# SPhotoDiode.net
KiCad netlist of a schematic drawn in EAGLE
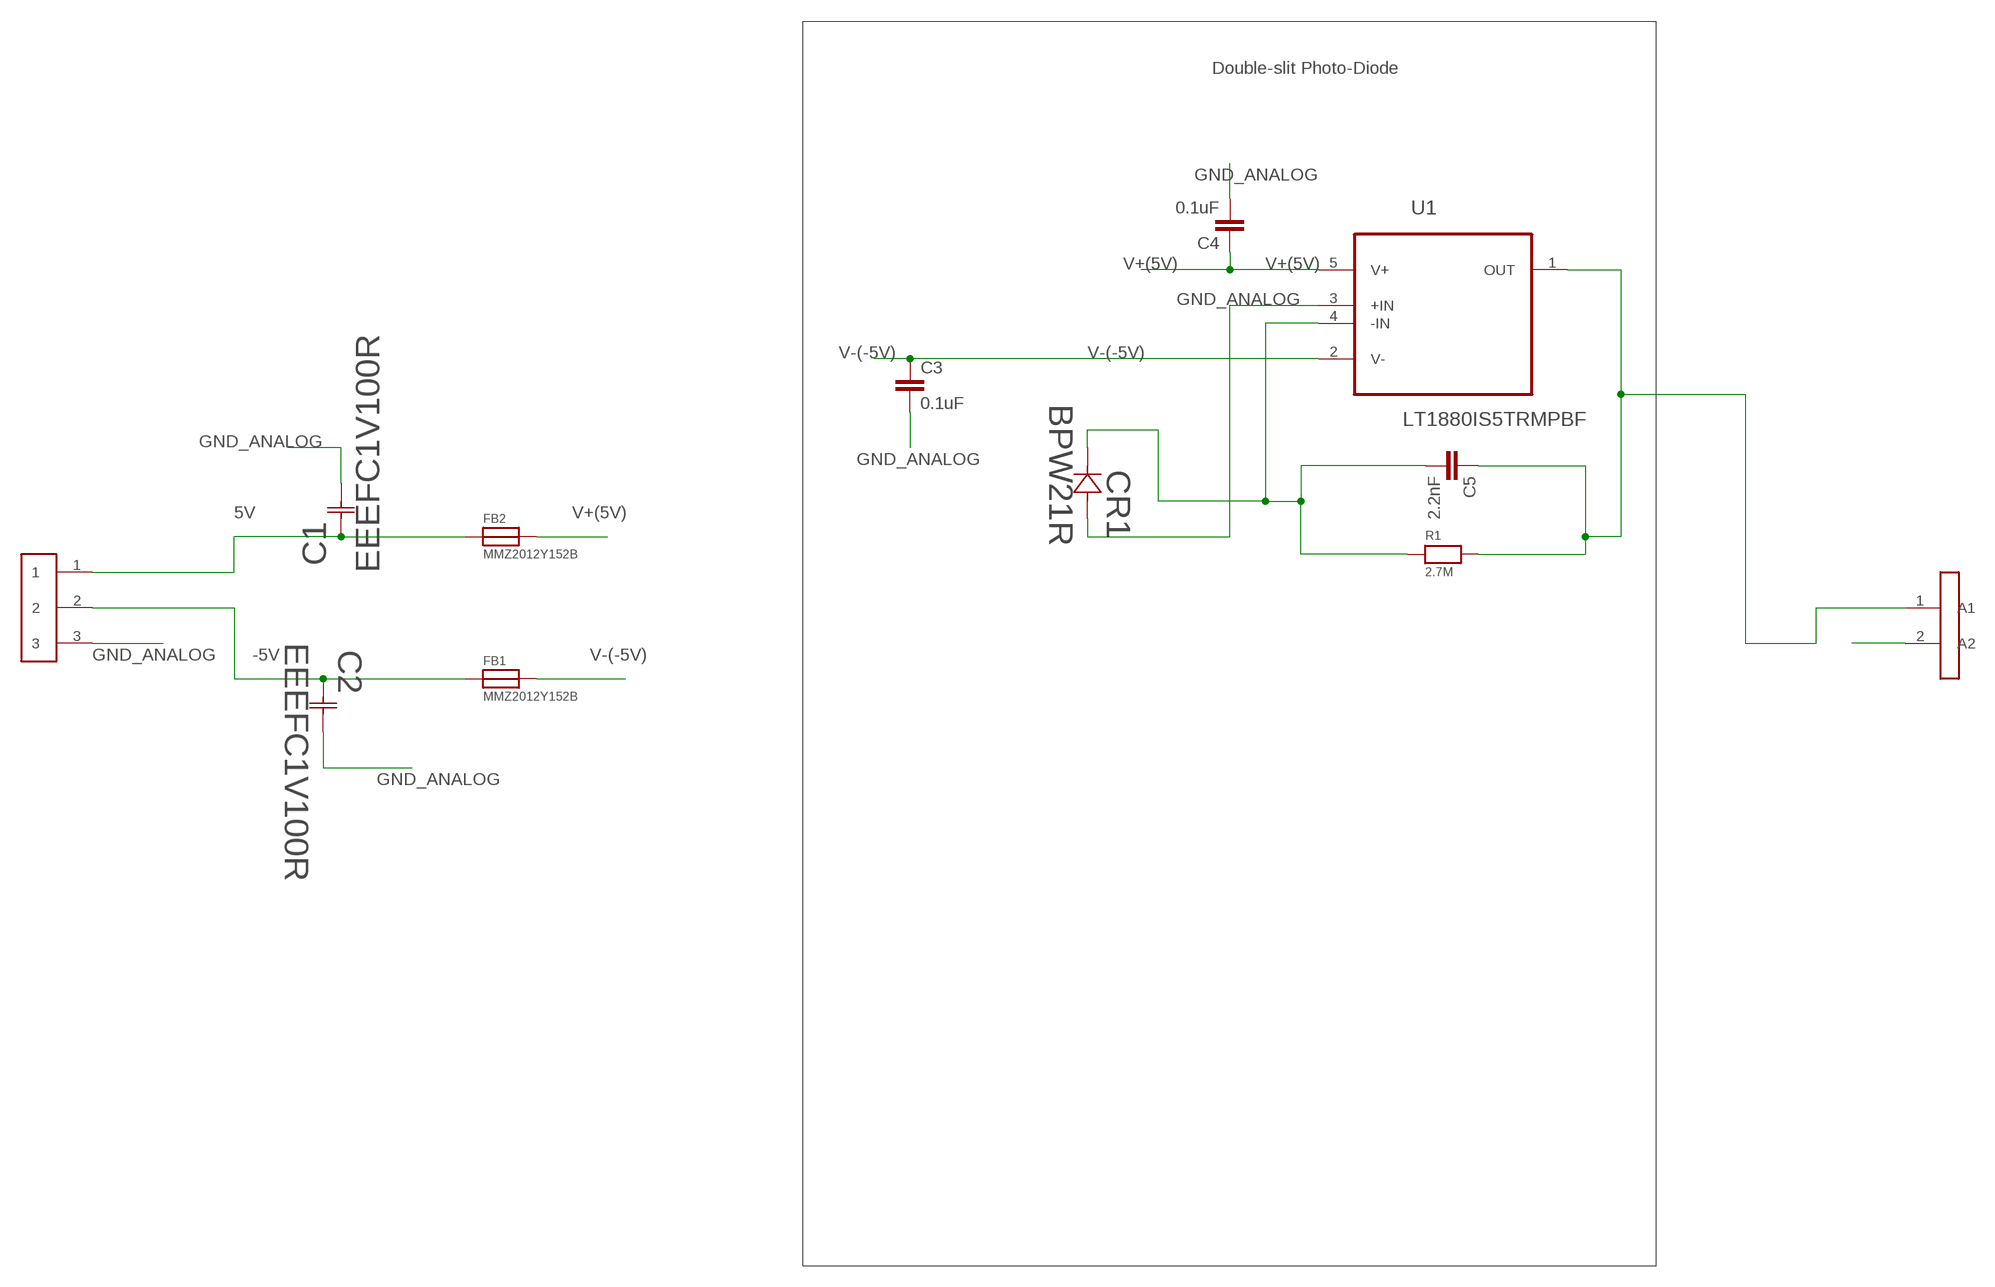
[diagram p0: schematic, sheet 1]

(export (version "E")
  (design (tool "Eeschema 10.0.6"))
  (components
    (comp (ref "C1")
      (value "EEEFC1V100R")
      (footprint "eagle-import:CAP_EEFC_C")
      (libsource (lib "eagle-import") (part "EEEFC1V100R"))
    )
    (comp (ref "C2")
      (value "EEEFC1V100R")
      (footprint "eagle-import:CAP_EEFC_C")
      (libsource (lib "eagle-import") (part "EEEFC1V100R"))
    )
    (comp (ref "C3")
      (value "0.1uF")
      (footprint "eagle-import:C0603")
      (libsource (lib "eagle-import") (part "C-EUC0603"))
    )
    (comp (ref "C4")
      (value "0.1uF")
      (footprint "eagle-import:C0603")
      (libsource (lib "eagle-import") (part "C-EUC0603"))
    )
    (comp (ref "C5")
      (value "2.2nF")
      (footprint "eagle-import:C0603")
      (libsource (lib "eagle-import") (part "C-EUC0603"))
    )
    (comp (ref "CR1")
      (value "BPW21R")
      (footprint "eagle-import:TO99_BPW20RF")
      (libsource (lib "eagle-import") (part "BPW21R"))
    )
    (comp (ref "FB1")
      (value "MMZ2012Y152B")
      (footprint "eagle-import:0805")
      (libsource (lib "eagle-import") (part "FERRITE0805"))
    )
    (comp (ref "FB2")
      (value "MMZ2012Y152B")
      (footprint "eagle-import:0805")
      (libsource (lib "eagle-import") (part "FERRITE0805"))
    )
    (comp (ref "J2")
      (value "22-28-8020")
      (footprint "eagle-import:22-28-8020")
      (fields (field (name "MANUFACTURER_PART_NUMBER") "22288020"))
      (libsource (lib "eagle-import") (part "22-28-8020"))
    )
    (comp (ref "R1")
      (value "2.7M")
      (footprint "eagle-import:0805")
      (libsource (lib "eagle-import") (part "RESISTOR0805"))
    )
    (comp (ref "U$2")
      (value "PINHD_SMD-3")
      (footprint "eagle-import:PINHD_SMD-3")
      (libsource (lib "eagle-import") (part "PINHD_SMD-3"))
    )
    (comp (ref "U1")
      (value "LT1880IS5TRMPBF")
      (footprint "eagle-import:SOT95P280X100-5N")
      (fields
        (field (name "DIGI-KEY_PART_NUMBER") "LT1880IS5#TRMPBFCT-ND")
        (field (name "MF") "Linear Technology")
        (field (name "MP") "LT1880IS5#TRMPBF")
      )
      (libsource (lib "eagle-import") (part "LT1880IS5TRMPBF"))
    )
  )
  (nets
    (net (code "1") (name "/-5V") (class "Default")
      (node (ref "C2") (pin "1") (pinfunction "11_1") (pintype "passive"))
      (node (ref "FB1") (pin "1") (pinfunction "P$1_1") (pintype "bidirectional"))
      (node (ref "U$2") (pin "2") (pinfunction "2_2") (pintype "bidirectional"))
    )
    (net (code "2") (name "/5V") (class "Default")
      (node (ref "C1") (pin "1") (pinfunction "11_1") (pintype "passive"))
      (node (ref "FB2") (pin "1") (pinfunction "P$1_1") (pintype "bidirectional"))
      (node (ref "U$2") (pin "1") (pinfunction "1_1") (pintype "bidirectional"))
    )
    (net (code "3") (name "/GND_ANALOG") (class "Default")
      (node (ref "C1") (pin "2") (pinfunction "22_2") (pintype "passive"))
      (node (ref "C2") (pin "2") (pinfunction "22_2") (pintype "passive"))
      (node (ref "C3") (pin "2") (pinfunction "2_2") (pintype "passive"))
      (node (ref "C4") (pin "2") (pinfunction "2_2") (pintype "passive"))
      (node (ref "CR1") (pin "2") (pinfunction "22_2") (pintype "passive"))
      (node (ref "J2") (pin "2") (pinfunction "A2_2") (pintype "passive"))
      (node (ref "U$2") (pin "3") (pinfunction "3_3") (pintype "bidirectional"))
      (node (ref "U1") (pin "3") (pinfunction "+IN_3") (pintype "input"))
    )
    (net (code "4") (name "/V+(5V)") (class "Default")
      (node (ref "C4") (pin "1") (pinfunction "1_1") (pintype "passive"))
      (node (ref "FB2") (pin "2") (pinfunction "P$2_2") (pintype "bidirectional"))
      (node (ref "U1") (pin "5") (pinfunction "V+_5") (pintype "power_in"))
    )
    (net (code "5") (name "/V-(-5V)") (class "Default")
      (node (ref "C3") (pin "1") (pinfunction "1_1") (pintype "passive"))
      (node (ref "FB1") (pin "2") (pinfunction "P$2_2") (pintype "bidirectional"))
      (node (ref "U1") (pin "2") (pinfunction "V-_2") (pintype "power_in"))
    )
    (net (code "6") (name "Net-(CR1-11)") (class "Default")
      (node (ref "C5") (pin "2") (pinfunction "2_2") (pintype "passive"))
      (node (ref "CR1") (pin "1") (pinfunction "11_1") (pintype "passive"))
      (node (ref "R1") (pin "1") (pinfunction "1_1") (pintype "passive"))
      (node (ref "U1") (pin "4") (pinfunction "-IN_4") (pintype "input"))
    )
    (net (code "7") (name "Net-(J2-A1)") (class "Default")
      (node (ref "C5") (pin "1") (pinfunction "1_1") (pintype "passive"))
      (node (ref "J2") (pin "1") (pinfunction "A1_1") (pintype "passive"))
      (node (ref "R1") (pin "2") (pinfunction "2_2") (pintype "passive"))
      (node (ref "U1") (pin "1") (pinfunction "OUT_1") (pintype "output"))
    )
  )
)
